# B293A_DAC.net
KiCad netlist of a schematic drawn in Altium Designer
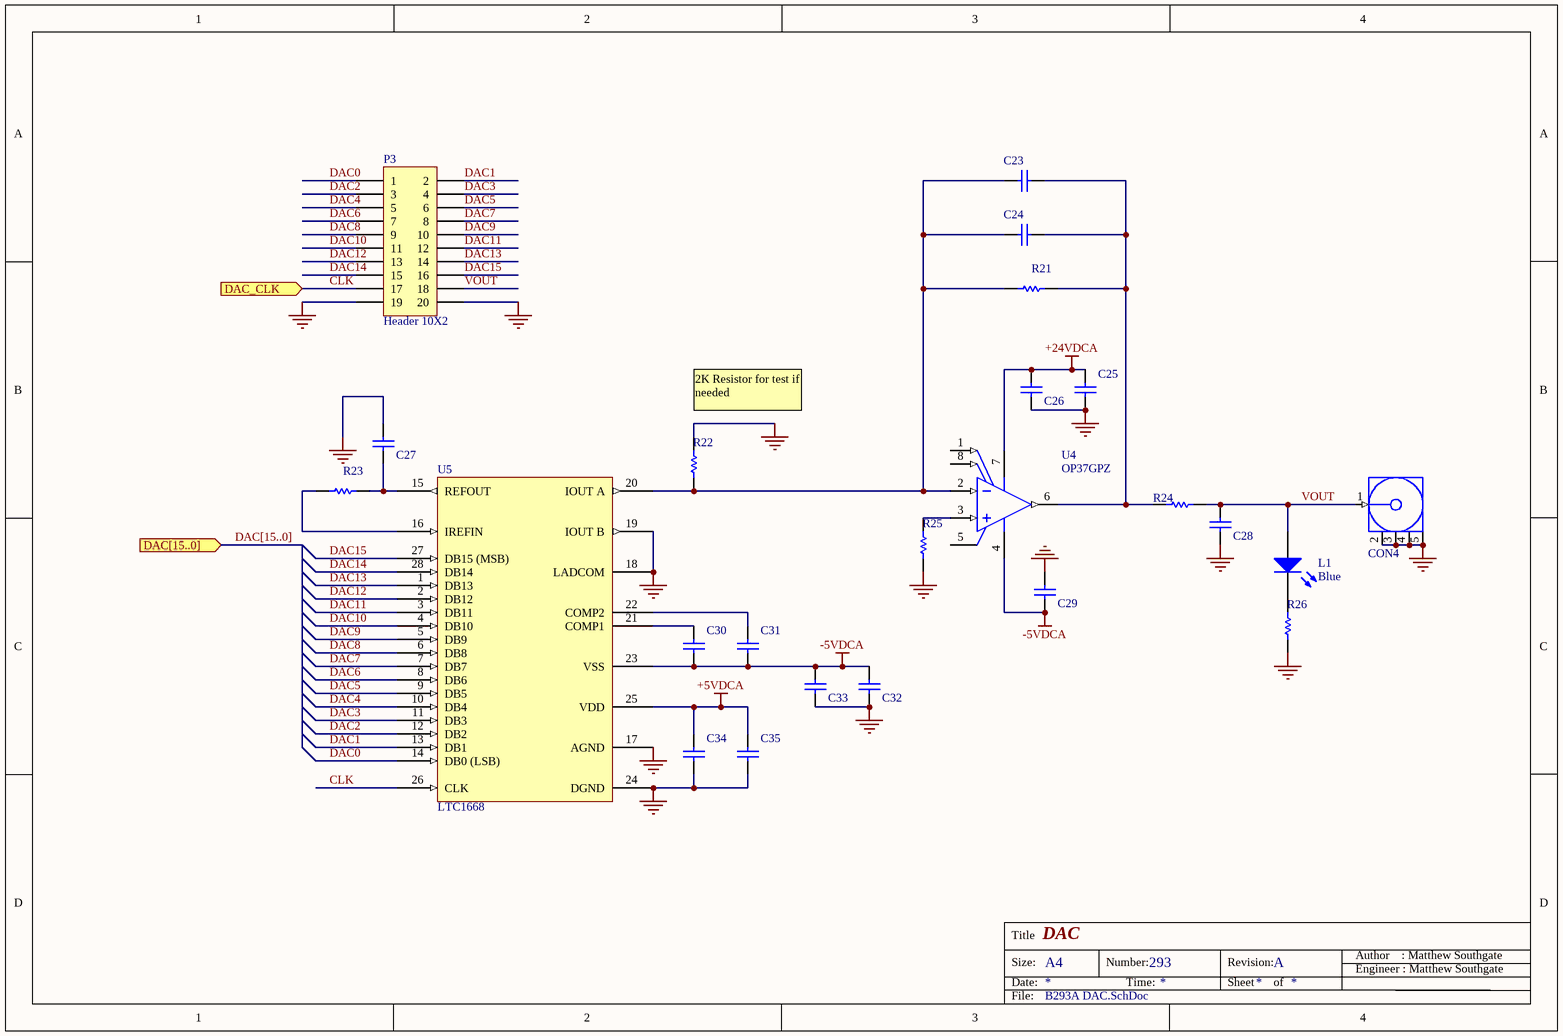
[diagram p0: B293A DAC.SchDoc]

(export (version "E")
  (design (tool "Eeschema 10.0.6"))
  (components
    (comp (ref "C23")
      (value "CAP 4.7nF 50V 0805(2012)")
      (footprint "CAPC0805(2012)75_M")
      (description "CAP 4.7nF 50V ±10% 0805 (2012 Metric) Thickness 0.75mm SMD")
      (fields (field (name "TOLERANCE") "±10%"))
      (libsource (lib "Altium Content Vault") (part "CAP"))
    )
    (comp (ref "C24")
      (value "CAP 470pF 50V 0805(2012)")
      (footprint "CAPC0805(2012)100_M")
      (description "CAP 470pF 50V ±10% 0805 (2012 Metric) Thickness 1mm SMD")
      (fields (field (name "TOLERANCE") "±10%"))
      (libsource (lib "Altium Content Vault") (part "CAP"))
    )
    (comp (ref "C25")
      (value "CAP 10uF 25V 0805(2012)")
      (footprint "CAPC0805(2012)145_N")
      (description "CAP 10uF 25V ±20% 0805 (2012 Metric) Thickness 1.45mm SMD")
      (fields (field (name "TOLERANCE") "±20%"))
      (libsource (lib "Altium Content Vault") (part "CAP"))
    )
    (comp (ref "C26")
      (value "CAP 100nF 50V 0805(2012)")
      (footprint "CAPC0805(2012)100_M")
      (description "CAP 100nF 50V ±20% 0805 (2012 Metric) Thickness 1mm SMD")
      (fields (field (name "TOLERANCE") "±20%"))
      (libsource (lib "Altium Content Vault") (part "CAP"))
    )
    (comp (ref "C27")
      (value "CAP 100nF 50V 0805(2012)")
      (footprint "CAPC0805(2012)100_M")
      (description "CAP 100nF 50V ±20% 0805 (2012 Metric) Thickness 1mm SMD")
      (fields (field (name "TOLERANCE") "±20%"))
      (libsource (lib "Altium Content Vault") (part "CAP"))
    )
    (comp (ref "C28")
      (value "CAP 100nF 50V 0805(2012)")
      (footprint "CAPC0805(2012)100_M")
      (description "CAP 100nF 50V ±20% 0805 (2012 Metric) Thickness 1mm SMD")
      (fields (field (name "TOLERANCE") "±20%"))
      (libsource (lib "Altium Content Vault") (part "CAP"))
    )
    (comp (ref "C29")
      (value "CAP 100nF 50V 0805(2012)")
      (footprint "CAPC0805(2012)100_M")
      (description "CAP 100nF 50V ±20% 0805 (2012 Metric) Thickness 1mm SMD")
      (fields (field (name "TOLERANCE") "±20%"))
      (libsource (lib "Altium Content Vault") (part "CAP"))
    )
    (comp (ref "C30")
      (value "CAP 100nF 50V 0805(2012)")
      (footprint "CAPC0805(2012)100_M")
      (description "CAP 100nF 50V ±20% 0805 (2012 Metric) Thickness 1mm SMD")
      (fields (field (name "TOLERANCE") "±20%"))
      (libsource (lib "Altium Content Vault") (part "CAP"))
    )
    (comp (ref "C31")
      (value "CAP 100nF 50V 0805(2012)")
      (footprint "CAPC0805(2012)100_M")
      (description "CAP 100nF 50V ±20% 0805 (2012 Metric) Thickness 1mm SMD")
      (fields (field (name "TOLERANCE") "±20%"))
      (libsource (lib "Altium Content Vault") (part "CAP"))
    )
    (comp (ref "C32")
      (value "CAP 10uF 25V 0805(2012)")
      (footprint "CAPC0805(2012)145_N")
      (description "CAP 10uF 25V ±20% 0805 (2012 Metric) Thickness 1.45mm SMD")
      (fields (field (name "TOLERANCE") "±20%"))
      (libsource (lib "Altium Content Vault") (part "CAP"))
    )
    (comp (ref "C33")
      (value "CAP 100nF 50V 0805(2012)")
      (footprint "CAPC0805(2012)100_M")
      (description "CAP 100nF 50V ±20% 0805 (2012 Metric) Thickness 1mm SMD")
      (fields (field (name "TOLERANCE") "±20%"))
      (libsource (lib "Altium Content Vault") (part "CAP"))
    )
    (comp (ref "C34")
      (value "CAP 100nF 50V 0805(2012)")
      (footprint "CAPC0805(2012)100_M")
      (description "CAP 100nF 50V ±20% 0805 (2012 Metric) Thickness 1mm SMD")
      (fields (field (name "TOLERANCE") "±20%"))
      (libsource (lib "Altium Content Vault") (part "CAP"))
    )
    (comp (ref "C35")
      (value "CAP 10uF 25V 0805(2012)")
      (footprint "CAPC0805(2012)145_N")
      (description "CAP 10uF 25V ±20% 0805 (2012 Metric) Thickness 1.45mm SMD")
      (fields (field (name "TOLERANCE") "±20%"))
      (libsource (lib "Altium Content Vault") (part "CAP"))
    )
    (comp (ref "CON4")
      (value "SMA Vertical")
      (footprint "Matt PCB Library:SMA Vertical")
      (fields (field (name "MANUFACTURERS PART NO") "5-1814832-1"))
      (libsource (lib "Matt SCH Library") (part "SMA Vertical"))
    )
    (comp (ref "L1")
      (value "Blue")
      (footprint "Matt PCB Library:1206 - LED")
      (description "LED, 1206, BLUE, 140MCD, 473NM")
      (fields
        (field (name "MANUFACTURER PART NUMBER") "598-8291-107F")
        (field (name "MANUFACTURER") "DIALIGHT")
      )
      (libsource (lib "Matt SCH Library") (part "LED 1206 BLUE"))
    )
    (comp (ref "P3")
      (value "Header 10X2")
      (footprint "HDR2X10")
      (description "Header, 10-Pin, Dual row")
      (fields (field (name "PUBLISHER") "Altium Limited"))
      (libsource (lib "Miscellaneous Connectors") (part "Header 10X2"))
    )
    (comp (ref "R21")
      (value "2K2 5% 0805(2012)")
      (footprint "RESC0805(2012)_L")
      (description "2K2 0.125W 5% 0805 (2012 Metric)  SMD")
      (fields (field (name "TOLERANCE") "5 %") (field (name "POWER") "0.125 W"))
      (libsource (lib "Altium Content Vault") (part "RES"))
    )
    (comp (ref "R22")
      (value "2K2 5% 0805(2012)")
      (footprint "RESC0805(2012)_L")
      (description "2K2 0.125W 5% 0805 (2012 Metric)  SMD")
      (fields (field (name "TOLERANCE") "5 %") (field (name "POWER") "0.125 W"))
      (libsource (lib "Altium Content Vault") (part "RES"))
    )
    (comp (ref "R23")
      (value "2K2 5% 0805(2012)")
      (footprint "RESC0805(2012)_L")
      (description "2K2 0.125W 5% 0805 (2012 Metric)  SMD")
      (fields (field (name "TOLERANCE") "5 %") (field (name "POWER") "0.125 W"))
      (libsource (lib "Altium Content Vault") (part "RES"))
    )
    (comp (ref "R24")
      (value "150R 5% 0805(2012)")
      (footprint "RESC0805(2012)_N")
      (description "150R 0.125W 5% 0805 (2012 Metric)  SMD")
      (fields (field (name "TOLERANCE") "5 %") (field (name "POWER") "0.125 W"))
      (libsource (lib "Altium Content Vault") (part "RES"))
    )
    (comp (ref "R25")
      (value "2K2 5% 0805(2012)")
      (footprint "RESC0805(2012)_L")
      (description "2K2 0.125W 5% 0805 (2012 Metric)  SMD")
      (fields (field (name "TOLERANCE") "5 %") (field (name "POWER") "0.125 W"))
      (libsource (lib "Altium Content Vault") (part "RES"))
    )
    (comp (ref "R26")
      (value "6K8 5% 0805(2012)")
      (footprint "RESC0805(2012)_L")
      (description "6K8 0.125W 5% 0805 (2012 Metric)  SMD")
      (fields (field (name "TOLERANCE") "5 %") (field (name "POWER") "0.125 W"))
      (libsource (lib "Altium Content Vault") (part "RES"))
    )
    (comp (ref "U4")
      (value "OP37GPZ")
      (footprint "ADI-N-8")
      (fields (field (name "MANUFACTURER") "Analog Devices"))
      (libsource (lib "Altium Content Vault") (part "ADI-OP177_X7-8"))
    )
    (comp (ref "U5")
      (value "LTC1668")
      (footprint "Matt PCB Library:SOP65P800X200-28N")
      (description "LINEAR TECHNOLOGY - LTC1668CG#PBF - IC, 16BIT DAC, 50MSPS, 28SSOP")
      (fields
        (field (name "MANUFACTURER") "LINEAR TECHNOLOGY")
        (field (name "MANUFACTURER PART NUMBER") "LTC1668CG#PBF")
      )
      (libsource (lib "Matt SCH Library") (part "LTC1668"))
    )
  )
  (nets
    (net (code "1") (name "+5VDCA") (class "Default")
      (node (ref "C34") (pin "2") (pinfunction "2_2") (pintype "passive"))
      (node (ref "C35") (pin "2") (pinfunction "2_2") (pintype "passive"))
      (node (ref "U5") (pin "25") (pinfunction "VDD_25") (pintype "power_in"))
    )
    (net (code "2") (name "+24VDCA") (class "Default")
      (node (ref "C25") (pin "2") (pinfunction "2_2") (pintype "passive"))
      (node (ref "C26") (pin "1") (pinfunction "1_1") (pintype "passive"))
      (node (ref "U4") (pin "7") (pinfunction "V+_7") (pintype "power_in"))
    )
    (net (code "3") (name "-5VDCA") (class "Default")
      (node (ref "C29") (pin "2") (pinfunction "2_2") (pintype "passive"))
      (node (ref "C30") (pin "1") (pinfunction "1_1") (pintype "passive"))
      (node (ref "C31") (pin "1") (pinfunction "1_1") (pintype "passive"))
      (node (ref "C32") (pin "1") (pinfunction "1_1") (pintype "passive"))
      (node (ref "C33") (pin "2") (pinfunction "2_2") (pintype "passive"))
      (node (ref "U4") (pin "4") (pinfunction "V-_4") (pintype "power_in"))
      (node (ref "U5") (pin "23") (pinfunction "VSS_23") (pintype "power_in"))
    )
    (net (code "4") (name "/CLK") (class "Default")
      (node (ref "P3") (pin "17") (pinfunction "17_17") (pintype "passive"))
      (node (ref "U5") (pin "26") (pinfunction "CLK_26") (pintype "input"))
    )
    (net (code "5") (name "/DAC0") (class "Default")
      (node (ref "P3") (pin "1") (pinfunction "1_1") (pintype "passive"))
      (node (ref "U5") (pin "14") (pinfunction "DB0_(LSB)_14") (pintype "input"))
    )
    (net (code "6") (name "/DAC1") (class "Default")
      (node (ref "P3") (pin "2") (pinfunction "2_2") (pintype "passive"))
      (node (ref "U5") (pin "13") (pinfunction "DB1_13") (pintype "input"))
    )
    (net (code "7") (name "/DAC2") (class "Default")
      (node (ref "P3") (pin "3") (pinfunction "3_3") (pintype "passive"))
      (node (ref "U5") (pin "12") (pinfunction "DB2_12") (pintype "input"))
    )
    (net (code "8") (name "/DAC3") (class "Default")
      (node (ref "P3") (pin "4") (pinfunction "4_4") (pintype "passive"))
      (node (ref "U5") (pin "11") (pinfunction "DB3_11") (pintype "input"))
    )
    (net (code "9") (name "/DAC4") (class "Default")
      (node (ref "P3") (pin "5") (pinfunction "5_5") (pintype "passive"))
      (node (ref "U5") (pin "10") (pinfunction "DB4_10") (pintype "input"))
    )
    (net (code "10") (name "/DAC5") (class "Default")
      (node (ref "P3") (pin "6") (pinfunction "6_6") (pintype "passive"))
      (node (ref "U5") (pin "9") (pinfunction "DB5_9") (pintype "input"))
    )
    (net (code "11") (name "/DAC6") (class "Default")
      (node (ref "P3") (pin "7") (pinfunction "7_7") (pintype "passive"))
      (node (ref "U5") (pin "8") (pinfunction "DB6_8") (pintype "input"))
    )
    (net (code "12") (name "/DAC7") (class "Default")
      (node (ref "P3") (pin "8") (pinfunction "8_8") (pintype "passive"))
      (node (ref "U5") (pin "7") (pinfunction "DB7_7") (pintype "input"))
    )
    (net (code "13") (name "/DAC8") (class "Default")
      (node (ref "P3") (pin "9") (pinfunction "9_9") (pintype "passive"))
      (node (ref "U5") (pin "6") (pinfunction "DB8_6") (pintype "input"))
    )
    (net (code "14") (name "/DAC9") (class "Default")
      (node (ref "P3") (pin "10") (pinfunction "10_10") (pintype "passive"))
      (node (ref "U5") (pin "5") (pinfunction "DB9_5") (pintype "input"))
    )
    (net (code "15") (name "/DAC10") (class "Default")
      (node (ref "P3") (pin "11") (pinfunction "11_11") (pintype "passive"))
      (node (ref "U5") (pin "4") (pinfunction "DB10_4") (pintype "input"))
    )
    (net (code "16") (name "/DAC11") (class "Default")
      (node (ref "P3") (pin "12") (pinfunction "12_12") (pintype "passive"))
      (node (ref "U5") (pin "3") (pinfunction "DB11_3") (pintype "input"))
    )
    (net (code "17") (name "/DAC12") (class "Default")
      (node (ref "P3") (pin "13") (pinfunction "13_13") (pintype "passive"))
      (node (ref "U5") (pin "2") (pinfunction "DB12_2") (pintype "input"))
    )
    (net (code "18") (name "/DAC13") (class "Default")
      (node (ref "P3") (pin "14") (pinfunction "14_14") (pintype "passive"))
      (node (ref "U5") (pin "1") (pinfunction "DB13_1") (pintype "input"))
    )
    (net (code "19") (name "/DAC14") (class "Default")
      (node (ref "P3") (pin "15") (pinfunction "15_15") (pintype "passive"))
      (node (ref "U5") (pin "28") (pinfunction "DB14_28") (pintype "input"))
    )
    (net (code "20") (name "/DAC15") (class "Default")
      (node (ref "P3") (pin "16") (pinfunction "16_16") (pintype "passive"))
      (node (ref "U5") (pin "27") (pinfunction "DB15_(MSB)_27") (pintype "input"))
    )
    (net (code "22") (name "/VOUT") (class "Default")
      (node (ref "C28") (pin "1") (pinfunction "1_1") (pintype "passive"))
      (node (ref "CON4") (pin "1") (pinfunction "Signal_1") (pintype "input"))
      (node (ref "L1") (pin "A") (pinfunction "A_A") (pintype "passive"))
      (node (ref "P3") (pin "18") (pinfunction "18_18") (pintype "passive"))
      (node (ref "R24") (pin "1") (pinfunction "1_1") (pintype "passive"))
    )
    (net (code "23") (name "GND") (class "Default")
      (node (ref "C25") (pin "1") (pinfunction "1_1") (pintype "passive"))
      (node (ref "C26") (pin "2") (pinfunction "2_2") (pintype "passive"))
      (node (ref "C27") (pin "1") (pinfunction "1_1") (pintype "passive"))
      (node (ref "C28") (pin "2") (pinfunction "2_2") (pintype "passive"))
      (node (ref "C29") (pin "1") (pinfunction "1_1") (pintype "passive"))
      (node (ref "C32") (pin "2") (pinfunction "2_2") (pintype "passive"))
      (node (ref "C33") (pin "1") (pinfunction "1_1") (pintype "passive"))
      (node (ref "C34") (pin "1") (pinfunction "1_1") (pintype "passive"))
      (node (ref "C35") (pin "1") (pinfunction "1_1") (pintype "passive"))
      (node (ref "CON4") (pin "2") (pinfunction "GND_2") (pintype "power_in"))
      (node (ref "CON4") (pin "3") (pinfunction "GND_3") (pintype "power_in"))
      (node (ref "CON4") (pin "4") (pinfunction "GND_4") (pintype "power_in"))
      (node (ref "CON4") (pin "5") (pinfunction "GND_5") (pintype "power_in"))
      (node (ref "P3") (pin "19") (pinfunction "19_19") (pintype "passive"))
      (node (ref "P3") (pin "20") (pinfunction "20_20") (pintype "passive"))
      (node (ref "R22") (pin "2") (pinfunction "2_2") (pintype "passive"))
      (node (ref "R25") (pin "1") (pinfunction "1_1") (pintype "passive"))
      (node (ref "R26") (pin "1") (pinfunction "1_1") (pintype "passive"))
      (node (ref "U5") (pin "17") (pinfunction "AGND_17") (pintype "power_in"))
      (node (ref "U5") (pin "18") (pinfunction "LADCOM_18") (pintype "power_in"))
      (node (ref "U5") (pin "19") (pinfunction "IOUT_B_19") (pintype "output"))
      (node (ref "U5") (pin "24") (pinfunction "DGND_24") (pintype "power_in"))
    )
    (net (code "24") (name "Net-(L1-PadK)") (class "Default")
      (node (ref "L1") (pin "K") (pinfunction "K_K") (pintype "passive"))
      (node (ref "R26") (pin "2") (pinfunction "2_2") (pintype "passive"))
    )
    (net (code "25") (name "Net-(U4-+IN)") (class "Default")
      (node (ref "R25") (pin "2") (pinfunction "2_2") (pintype "passive"))
      (node (ref "U4") (pin "3") (pinfunction "+IN_3") (pintype "input"))
    )
    (net (code "26") (name "Net-(U4--IN)") (class "Default")
      (node (ref "C23") (pin "2") (pinfunction "2_2") (pintype "passive"))
      (node (ref "C24") (pin "2") (pinfunction "2_2") (pintype "passive"))
      (node (ref "R21") (pin "1") (pinfunction "1_1") (pintype "passive"))
      (node (ref "R22") (pin "1") (pinfunction "1_1") (pintype "passive"))
      (node (ref "U4") (pin "2") (pinfunction "-IN_2") (pintype "input"))
      (node (ref "U5") (pin "20") (pinfunction "IOUT_A_20") (pintype "output"))
    )
    (net (code "27") (name "Net-(U4-OUT)") (class "Default")
      (node (ref "C23") (pin "1") (pinfunction "1_1") (pintype "passive"))
      (node (ref "C24") (pin "1") (pinfunction "1_1") (pintype "passive"))
      (node (ref "R21") (pin "2") (pinfunction "2_2") (pintype "passive"))
      (node (ref "R24") (pin "2") (pinfunction "2_2") (pintype "passive"))
      (node (ref "U4") (pin "6") (pinfunction "OUT_6") (pintype "output"))
    )
    (net (code "28") (name "Net-(U5-COMP1)") (class "Default")
      (node (ref "C30") (pin "2") (pinfunction "2_2") (pintype "passive"))
      (node (ref "U5") (pin "21") (pinfunction "COMP1_21") (pintype "passive"))
    )
    (net (code "29") (name "Net-(U5-COMP2)") (class "Default")
      (node (ref "C31") (pin "2") (pinfunction "2_2") (pintype "passive"))
      (node (ref "U5") (pin "22") (pinfunction "COMP2_22") (pintype "passive"))
    )
    (net (code "30") (name "Net-(U5-IREFIN)") (class "Default")
      (node (ref "R23") (pin "1") (pinfunction "1_1") (pintype "passive"))
      (node (ref "U5") (pin "16") (pinfunction "IREFIN_16") (pintype "input"))
    )
    (net (code "31") (name "Net-(U5-REFOUT)") (class "Default")
      (node (ref "C27") (pin "2") (pinfunction "2_2") (pintype "passive"))
      (node (ref "R23") (pin "2") (pinfunction "2_2") (pintype "passive"))
      (node (ref "U5") (pin "15") (pinfunction "REFOUT_15") (pintype "output"))
    )
    (net (code "32") (name "unconnected-(U4-NC-Pad5)") (class "Default")
      (node (ref "U4") (pin "5") (pinfunction "NC_5") (pintype "passive"))
    )
    (net (code "33") (name "unconnected-(U4-VOS_TRIM-Pad1)") (class "Default")
      (node (ref "U4") (pin "1") (pinfunction "VOS_TRIM_1") (pintype "input"))
    )
    (net (code "34") (name "unconnected-(U4-VOS_TRIM-Pad8)") (class "Default")
      (node (ref "U4") (pin "8") (pinfunction "VOS_TRIM_8") (pintype "input"))
    )
  )
)
